# ATTiny85.net
KiCad netlist of a schematic drawn in Altium Designer
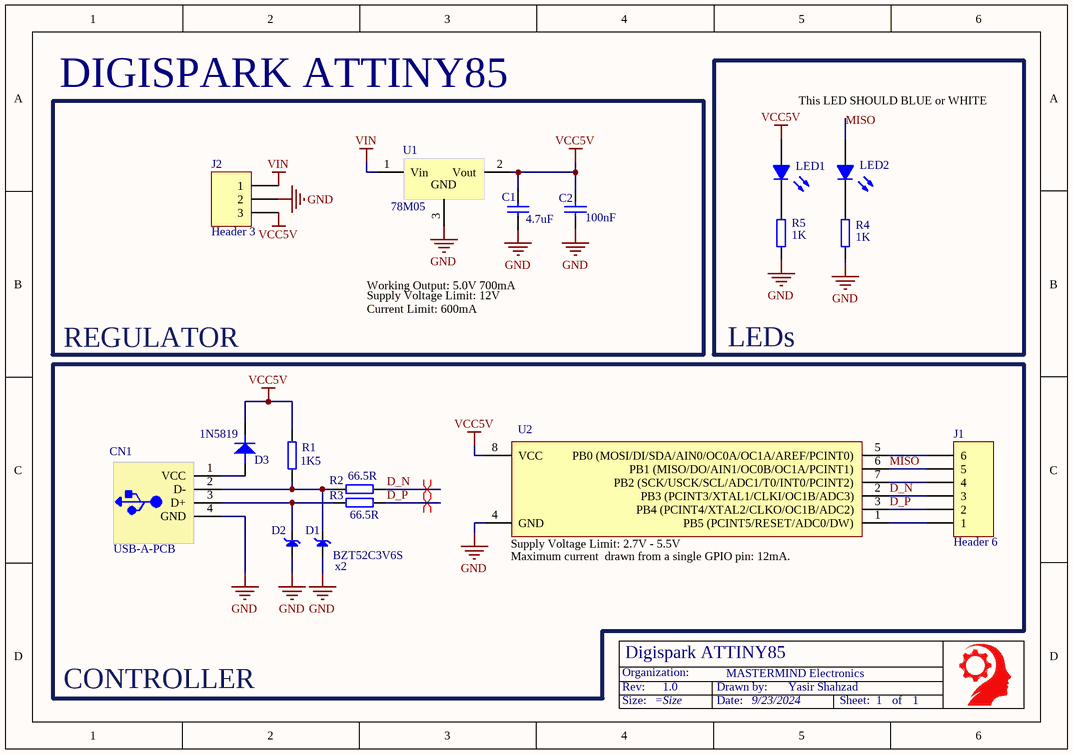
[diagram p0: ATTiny85.SchDoc]

(export (version "E")
  (design (tool "Eeschema 10.0.6"))
  (components
    (comp (ref "*")
      (value "TitleBlock")
      (description "Title Block for Schematic Sheets")
      (libsource (lib "mastermind") (part "TitleBlock"))
    )
    (comp (ref "C1")
      (value "4.7uF")
      (footprint "C0805")
      (description "Capacitor, X5R, ±10%, 6.3V")
      (fields (field (name "MANUFACTURER") "N.A."))
      (libsource (lib "mastermind") (part "Cap_0805"))
    )
    (comp (ref "C2")
      (value "100nF")
      (footprint "C0603")
      (description "Capacitor, X5R, ±10%, 6.3V")
      (fields
        (field (name "PART NUMBER") "C0603-N.C.")
        (field (name "MANUFACTURER") "N.A.")
        (field (name "PUBLISHER") "Nordic Semiconductor")
      )
      (libsource (lib "mastermind") (part "Cap_0603"))
    )
    (comp (ref "CN1")
      (value "USB ConnectorsUSBMINIB - Surface Mount Female Mini-B USB Connector 4UConnector: 06564   By microbuilder.euThru-hole RA Female Mini-B USB Connector 4UConnector: 18732   By ladyada.net")
      (footprint "USB-A-PCB")
      (fields (field (name "NAME") "USB-A-PCB"))
      (libsource (lib "mastermind") (part "USB-A-MALE_PCB"))
    )
    (comp (ref "D1")
      (value "BZT52C3V6S")
      (footprint "SOD-323")
      (description "Independent Type 200mW 3.6V~3.8V 3.4V SOD-323 Zener Diodes ROHS")
      (fields (field (name "MANUFACTURER") "YFW(佑风微)"))
      (libsource (lib "mastermind") (part "DIODE-BZT52C3V6S"))
    )
    (comp (ref "D2")
      (value "BZT52C3V6S")
      (footprint "SOD-323")
      (description "Independent Type 200mW 3.6V~3.8V 3.4V SOD-323 Zener Diodes ROHS")
      (fields (field (name "MANUFACTURER") "YFW(佑风微)"))
      (libsource (lib "mastermind") (part "DIODE-BZT52C3V6S"))
    )
    (comp (ref "D3")
      (value "1N5819")
      (footprint "SOD-123HE1_L3.0-W2.0-LS3.7-RD")
      (description "Schottky Diode")
      (libsource (lib "mastermind") (part "DIODE-SOD123"))
    )
    (comp (ref "J1")
      (value "Header 6")
      (footprint "HDR1X6")
      (description "Header, 6-Pin")
      (fields (field (name "PUBLISHER") "Altium Limited"))
      (libsource (lib "Miscellaneous Connectors") (part "Header 6"))
    )
    (comp (ref "J2")
      (value "Header 3")
      (footprint "HDR1X3")
      (description "Header, 3-Pin")
      (fields (field (name "PUBLISHER") "Altium Limited"))
      (libsource (lib "Miscellaneous Connectors") (part "Header 3"))
    )
    (comp (ref "LED1")
      (value "LED Red")
      (footprint "CHIP-LED0603")
      (description "SMD lamp beads")
      (libsource (lib "mastermind") (part "LEDCHIP-LED0603"))
    )
    (comp (ref "LED2")
      (value "LED Green")
      (footprint "CHIP-LED0603")
      (description "SMD lamp beads")
      (libsource (lib "mastermind") (part "LEDCHIP-LED0603"))
    )
    (comp (ref "R1")
      (value "1.5kΩ")
      (footprint "R0603-NO")
      (description "Resistor, ±1%, 0.100W")
      (fields
        (field (name "PART NUMBER") "R0603-N.C.Ω")
        (field (name "MANUFACTURER") "N.A.")
        (field (name "PUBLISHER") "Nordic Semiconductor")
      )
      (libsource (lib "") (part "Res_0603_3"))
    )
    (comp (ref "R2")
      (value "66.5Ω")
      (footprint "R0603-NO")
      (description "Resistor, ±1%, 0.100W")
      (fields
        (field (name "PART NUMBER") "R0603-N.C.Ω")
        (field (name "MANUFACTURER") "N.A.")
        (field (name "PUBLISHER") "Nordic Semiconductor")
      )
      (libsource (lib "mastermind") (part "Res_0603"))
    )
    (comp (ref "R3")
      (value "66.5Ω")
      (footprint "R0603-NO")
      (description "Resistor, ±1%, 0.100W")
      (fields
        (field (name "PART NUMBER") "R0603-N.C.Ω")
        (field (name "MANUFACTURER") "N.A.")
        (field (name "PUBLISHER") "Nordic Semiconductor")
      )
      (libsource (lib "") (part "Res_0603_2"))
    )
    (comp (ref "R4")
      (value "1kΩ")
      (footprint "R0603-NO")
      (description "Resistor, ±1%, 0.100W")
      (fields
        (field (name "PART NUMBER") "R0603-N.C.Ω")
        (field (name "MANUFACTURER") "N.A.")
        (field (name "PUBLISHER") "Nordic Semiconductor")
      )
      (libsource (lib "") (part "Res_0603_1"))
    )
    (comp (ref "R5")
      (value "1kΩ")
      (footprint "R0603-NO")
      (description "Resistor, ±1%, 0.100W")
      (fields
        (field (name "PART NUMBER") "R0603-N.C.Ω")
        (field (name "MANUFACTURER") "N.A.")
        (field (name "PUBLISHER") "Nordic Semiconductor")
      )
      (libsource (lib "") (part "Res_0603_1"))
    )
    (comp (ref "U1")
      (value "78M05")
      (footprint "TO252")
      (description "5V Linear Regulator")
      (libsource (lib "mastermind") (part "REG-7805_TO252"))
    )
    (comp (ref "U2")
      (value "ATTINY85-20SU")
      (footprint "SOIC8_208MIL")
      (description "8KB 2.7V~5.5V AVR 512Byte 20MHz FLASH 6 SOIC-8-208mil Microcontrollers (MCU/MPU/SOC) ROHS")
      (fields (field (name "MANUFACTURER") "MICROCHIP(美国微芯)"))
      (libsource (lib "mastermind") (part "ATTINY85-20SU"))
    )
  )
  (nets
    (net (code "1") (name "/D_N") (class "Default")
      (node (ref "J1") (pin "3") (pinfunction "3_3") (pintype "passive"))
      (node (ref "R2") (pin "2") (pinfunction "2_2") (pintype "passive"))
      (node (ref "U2") (pin "2") (pinfunction "PB3_(PCINT3/XTAL1/CLKI/OC1B/ADC3)_2") (pintype "passive"))
    )
    (net (code "2") (name "/D_P") (class "Default")
      (node (ref "J1") (pin "2") (pinfunction "2_2") (pintype "passive"))
      (node (ref "R3") (pin "1") (pinfunction "1_1") (pintype "passive"))
      (node (ref "U2") (pin "3") (pinfunction "PB4_(PCINT4/XTAL2/CLKO/OC1B/ADC2)_3") (pintype "passive"))
    )
    (net (code "3") (name "/MISO") (class "Default")
      (node (ref "J1") (pin "5") (pinfunction "5_5") (pintype "passive"))
      (node (ref "LED2") (pin "A") (pinfunction "A_A") (pintype "passive"))
      (node (ref "U2") (pin "6") (pinfunction "PB1_(MISO/DO/AIN1/OC0B/OC1A/PCINT1)_6") (pintype "passive"))
    )
    (net (code "4") (name "GND") (class "Default")
      (node (ref "C1") (pin "2") (pinfunction "2_2") (pintype "passive"))
      (node (ref "C2") (pin "2") (pinfunction "2_2") (pintype "passive"))
      (node (ref "CN1") (pin "4") (pinfunction "GND_4") (pintype "passive"))
      (node (ref "D1") (pin "A") (pinfunction "A_A") (pintype "power_in"))
      (node (ref "D2") (pin "A") (pinfunction "A_A") (pintype "power_in"))
      (node (ref "J2") (pin "2") (pinfunction "2_2") (pintype "passive"))
      (node (ref "R4") (pin "2") (pinfunction "2_2") (pintype "passive"))
      (node (ref "R5") (pin "2") (pinfunction "2_2") (pintype "passive"))
      (node (ref "U1") (pin "3") (pinfunction "GND_3") (pintype "passive"))
      (node (ref "U2") (pin "4") (pinfunction "GND_4") (pintype "passive"))
    )
    (net (code "5") (name "Net-(CN1-D+)") (class "Default")
      (node (ref "CN1") (pin "3") (pinfunction "D+_3") (pintype "passive"))
      (node (ref "D2") (pin "K") (pinfunction "C_K") (pintype "power_in"))
      (node (ref "R3") (pin "2") (pinfunction "2_2") (pintype "passive"))
    )
    (net (code "6") (name "Net-(CN1-D-)") (class "Default")
      (node (ref "CN1") (pin "2") (pinfunction "D-_2") (pintype "passive"))
      (node (ref "D1") (pin "K") (pinfunction "C_K") (pintype "power_in"))
      (node (ref "R1") (pin "1") (pinfunction "1_1") (pintype "passive"))
      (node (ref "R2") (pin "1") (pinfunction "1_1") (pintype "passive"))
    )
    (net (code "7") (name "Net-(CN1-VCC)") (class "Default")
      (node (ref "CN1") (pin "1") (pinfunction "VCC_1") (pintype "power_in"))
      (node (ref "D3") (pin "2") (pinfunction "A_2") (pintype "passive"))
    )
    (net (code "8") (name "Net-(LED1-K)") (class "Default")
      (node (ref "LED1") (pin "C") (pinfunction "K_C") (pintype "passive"))
      (node (ref "R5") (pin "1") (pinfunction "1_1") (pintype "passive"))
    )
    (net (code "9") (name "Net-(LED2-K)") (class "Default")
      (node (ref "LED2") (pin "C") (pinfunction "K_C") (pintype "passive"))
      (node (ref "R4") (pin "1") (pinfunction "1_1") (pintype "passive"))
    )
    (net (code "10") (name "Net-(U2-PB0_(MOSI{slash}DI{slash}SDA{slash}AIN0{slash}OC0A{slash}OC1A{slash}AREF{slash}PCINT0))") (class "Default")
      (node (ref "J1") (pin "6") (pinfunction "6_6") (pintype "passive"))
      (node (ref "U2") (pin "5") (pinfunction "PB0_(MOSI/DI/SDA/AIN0/OC0A/OC1A/AREF/PCINT0)_5") (pintype "passive"))
    )
    (net (code "11") (name "Net-(U2-PB2_(SCK{slash}USCK{slash}SCL{slash}ADC1{slash}T0{slash}INT0{slash}PCINT2))") (class "Default")
      (node (ref "J1") (pin "4") (pinfunction "4_4") (pintype "passive"))
      (node (ref "U2") (pin "7") (pinfunction "PB2_(SCK/USCK/SCL/ADC1/T0/INT0/PCINT2)_7") (pintype "passive"))
    )
    (net (code "12") (name "Net-(U2-PB5_(PCINT5{slash}RESET{slash}ADC0{slash}DW))") (class "Default")
      (node (ref "J1") (pin "1") (pinfunction "1_1") (pintype "passive"))
      (node (ref "U2") (pin "1") (pinfunction "PB5_(PCINT5/RESET/ADC0/DW)_1") (pintype "passive"))
    )
    (net (code "13") (name "VCC5V") (class "Default")
      (node (ref "C1") (pin "1") (pinfunction "1_1") (pintype "passive"))
      (node (ref "C2") (pin "1") (pinfunction "1_1") (pintype "passive"))
      (node (ref "D3") (pin "1") (pinfunction "C_1") (pintype "passive"))
      (node (ref "J2") (pin "3") (pinfunction "3_3") (pintype "passive"))
      (node (ref "LED1") (pin "A") (pinfunction "A_A") (pintype "passive"))
      (node (ref "R1") (pin "2") (pinfunction "2_2") (pintype "passive"))
      (node (ref "U1") (pin "2") (pinfunction "Vout_2") (pintype "passive"))
      (node (ref "U2") (pin "8") (pinfunction "VCC_8") (pintype "passive"))
    )
    (net (code "14") (name "VIN") (class "Default")
      (node (ref "J2") (pin "1") (pinfunction "1_1") (pintype "passive"))
      (node (ref "U1") (pin "1") (pinfunction "Vin_1") (pintype "passive"))
    )
  )
)
